# TopLevel.net
KiCad netlist of a schematic drawn in Altium Designer
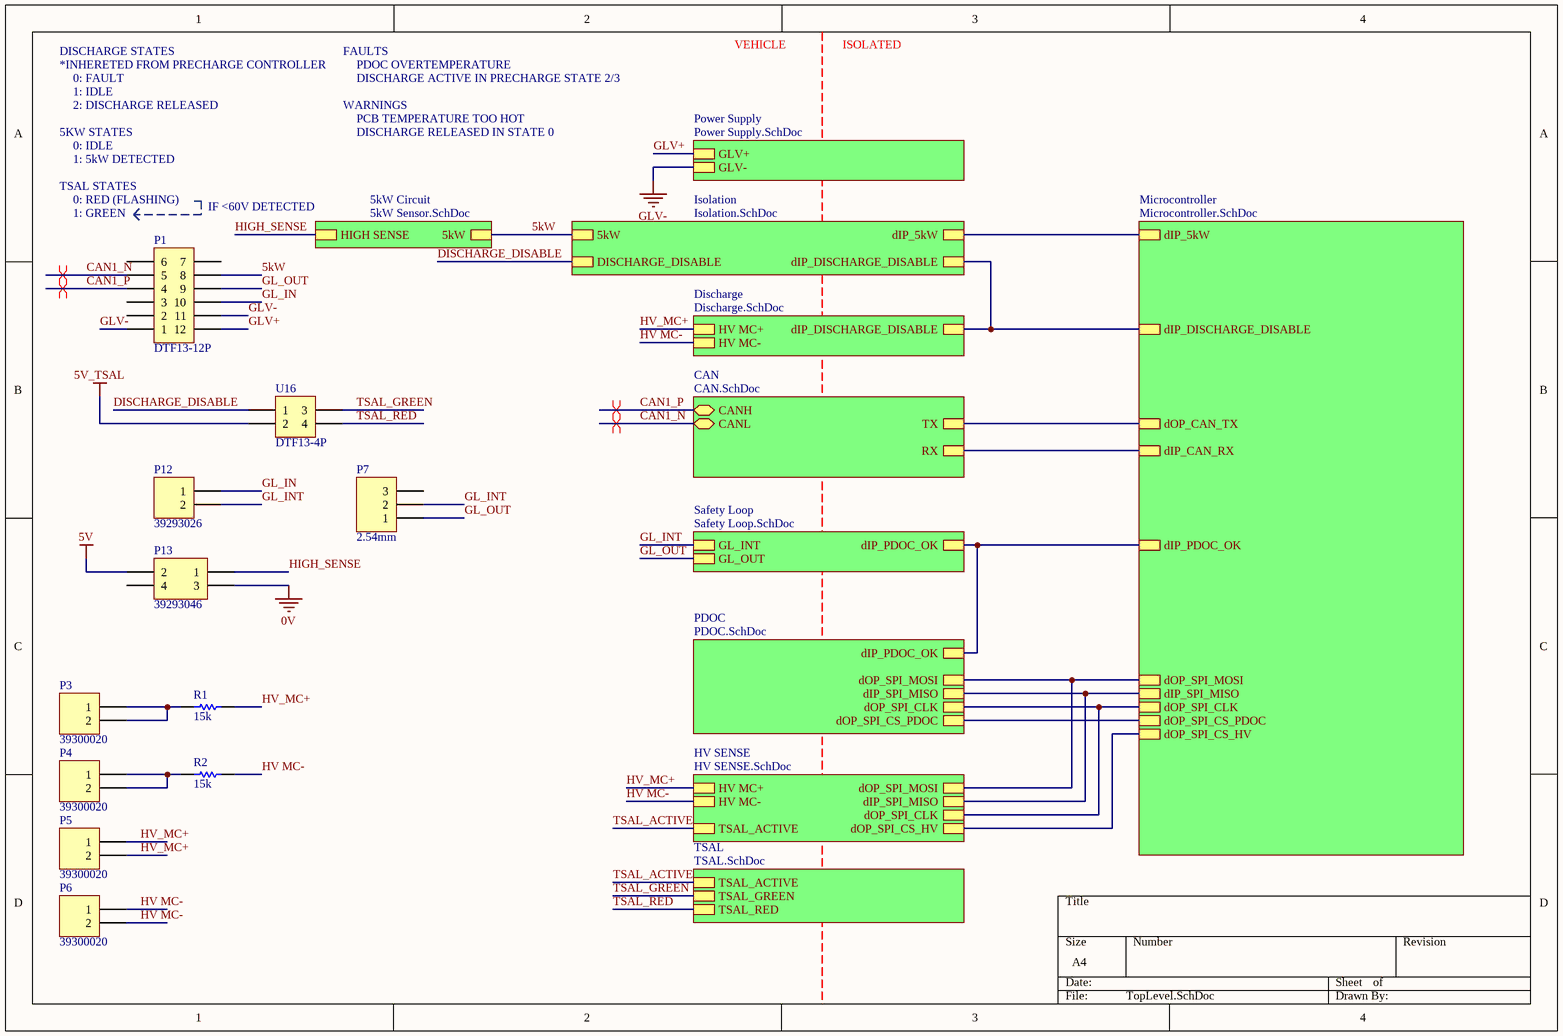
[diagram p0: TopLevel.SchDoc]

(export (version "E")
  (design (tool "Eeschema 10.0.6"))
  (components
    (comp (ref "P1")
      (value "DTF13-12P")
      (footprint "DTF13-12P")
      (fields (field (name "DIGIKEY PART NUMBER") "1734-1861-ND") (field (name "CONTACT") "Copper Alloy"))
      (libsource (lib "ts_standard_connectors") (part "DT13-12P"))
    )
    (comp (ref "P3")
      (value "39300020")
      (footprint "39300020")
      (fields (field (name "DIGIKEY PART NUMBER") "WM21351-ND") (field (name "CONTACT") "Tin"))
      (libsource (lib "ts_standard_connectors") (part "2"))
    )
    (comp (ref "P4")
      (value "39300020")
      (footprint "39300020")
      (fields (field (name "DIGIKEY PART NUMBER") "WM21351-ND") (field (name "CONTACT") "Tin"))
      (libsource (lib "ts_standard_connectors") (part "2"))
    )
    (comp (ref "P5")
      (value "39300020")
      (footprint "39300020")
      (fields (field (name "DIGIKEY PART NUMBER") "WM21351-ND") (field (name "CONTACT") "Tin"))
      (libsource (lib "ts_standard_connectors") (part "2"))
    )
    (comp (ref "P6")
      (value "39300020")
      (footprint "39300020")
      (fields (field (name "DIGIKEY PART NUMBER") "WM21351-ND") (field (name "CONTACT") "Tin"))
      (libsource (lib "ts_standard_connectors") (part "2"))
    )
    (comp (ref "P7")
      (value "2.54mm")
      (footprint "TH 2.54mm Header 1x3")
      (fields (field (name "PART NUMBER") "TH 2.54mm Header 1x3") (field (name "CONTACT") "NA"))
      (libsource (lib "ts_standard_connectors") (part "Header 1x3"))
    )
    (comp (ref "P12")
      (value "39293026")
      (footprint "39293026")
      (fields (field (name "DIGIKEY PART NUMBER") "WM3843-ND") (field (name "CONTACT") "Tin"))
      (libsource (lib "ts_standard_connectors") (part "2"))
    )
    (comp (ref "P13")
      (value "39293046")
      (footprint "39293046")
      (fields (field (name "DIGIKEY PART NUMBER") "WM3844-ND") (field (name "CONTACT") "Tin"))
      (libsource (lib "ts_standard_connectors") (part "4"))
    )
    (comp (ref "R1")
      (value "15k")
      (footprint "TE_SMF7")
      (fields
        (field (name "PART NUMBER") "SMF715KJ")
        (field (name "MANUFACTURER") "TE")
        (field (name "TOLERANCE") "0.05")
      )
      (libsource (lib "ts_standard_library") (part "Resistor"))
    )
    (comp (ref "R2")
      (value "15k")
      (footprint "TE_SMF7")
      (fields
        (field (name "PART NUMBER") "SMF715KJ")
        (field (name "MANUFACTURER") "TE")
        (field (name "TOLERANCE") "0.05")
      )
      (libsource (lib "ts_standard_library") (part "Resistor"))
    )
    (comp (ref "U16")
      (value "DTF13-4P")
      (footprint "DTF13-4P")
      (fields (field (name "DIGIKEY PART NUMBER") "1734-1646-ND") (field (name "CONTACT") "Copper Alloy"))
      (libsource (lib "ts_standard_connectors") (part "DT13-4P"))
    )
  )
  (nets
    (net (code "1") (name "/5kW") (class "Default")
      (node (ref "P1") (pin "8") (pinfunction "8_8") (pintype "passive"))
    )
    (net (code "2") (name "/CAN1_N") (class "Default")
      (node (ref "P1") (pin "5") (pinfunction "5_5") (pintype "power_in"))
    )
    (net (code "3") (name "/CAN1_P") (class "Default")
      (node (ref "P1") (pin "4") (pinfunction "4_4") (pintype "power_in"))
    )
    (net (code "4") (name "/DISCHARGE_DISABLE") (class "Default")
      (node (ref "U16") (pin "1") (pinfunction "1_1") (pintype "power_in"))
    )
    (net (code "5") (name "/GLV+") (class "Default")
      (node (ref "P1") (pin "12") (pinfunction "12_12") (pintype "passive"))
    )
    (net (code "6") (name "/GL_IN") (class "Default")
      (node (ref "P1") (pin "10") (pinfunction "10_10") (pintype "passive"))
      (node (ref "P12") (pin "1") (pinfunction "1_1") (pintype "passive"))
    )
    (net (code "7") (name "/GL_INT") (class "Default")
      (node (ref "P12") (pin "2") (pinfunction "2_2") (pintype "passive"))
      (node (ref "P7") (pin "2") (pinfunction "2_2") (pintype "passive"))
    )
    (net (code "8") (name "/GL_OUT") (class "Default")
      (node (ref "P1") (pin "9") (pinfunction "9_9") (pintype "passive"))
      (node (ref "P7") (pin "1") (pinfunction "1_1") (pintype "passive"))
    )
    (net (code "9") (name "/HIGH_SENSE") (class "Default")
      (node (ref "P13") (pin "1") (pinfunction "1_1") (pintype "passive"))
    )
    (net (code "10") (name "/HV MC-") (class "Default")
      (node (ref "P6") (pin "1") (pinfunction "1_1") (pintype "passive"))
      (node (ref "P6") (pin "2") (pinfunction "2_2") (pintype "passive"))
      (node (ref "R2") (pin "2") (pinfunction "2_2") (pintype "passive"))
    )
    (net (code "11") (name "/HV_MC+") (class "Default")
      (node (ref "P5") (pin "1") (pinfunction "1_1") (pintype "passive"))
      (node (ref "P5") (pin "2") (pinfunction "2_2") (pintype "passive"))
      (node (ref "R1") (pin "2") (pinfunction "2_2") (pintype "passive"))
    )
    (net (code "14") (name "/TSAL_GREEN") (class "Default")
      (node (ref "U16") (pin "3") (pinfunction "3_3") (pintype "passive"))
    )
    (net (code "15") (name "/TSAL_RED") (class "Default")
      (node (ref "U16") (pin "4") (pinfunction "4_4") (pintype "passive"))
    )
    (net (code "25") (name "0V") (class "Default")
      (node (ref "P13") (pin "3") (pinfunction "3_3") (pintype "passive"))
    )
    (net (code "26") (name "5V") (class "Default")
      (node (ref "P13") (pin "2") (pinfunction "2_2") (pintype "passive"))
    )
    (net (code "27") (name "5V_TSAL") (class "Default")
      (node (ref "U16") (pin "2") (pinfunction "2_2") (pintype "power_in"))
    )
    (net (code "28") (name "GLV-") (class "Default")
      (node (ref "P1") (pin "1") (pinfunction "1_1") (pintype "power_in"))
      (node (ref "P1") (pin "11") (pinfunction "11_11") (pintype "passive"))
    )
    (net (code "29") (name "Net-(P3-Pad1)") (class "Default")
      (node (ref "P3") (pin "1") (pinfunction "1_1") (pintype "passive"))
      (node (ref "P3") (pin "2") (pinfunction "2_2") (pintype "passive"))
      (node (ref "R1") (pin "1") (pinfunction "1_1") (pintype "passive"))
    )
    (net (code "30") (name "Net-(P4-Pad1)") (class "Default")
      (node (ref "P4") (pin "1") (pinfunction "1_1") (pintype "passive"))
      (node (ref "P4") (pin "2") (pinfunction "2_2") (pintype "passive"))
      (node (ref "R2") (pin "1") (pinfunction "1_1") (pintype "passive"))
    )
    (net (code "31") (name "unconnected-(P1-Pad2)") (class "Default")
      (node (ref "P1") (pin "2") (pinfunction "2_2") (pintype "power_in"))
    )
    (net (code "32") (name "unconnected-(P1-Pad3)") (class "Default")
      (node (ref "P1") (pin "3") (pinfunction "3_3") (pintype "power_in"))
    )
    (net (code "33") (name "unconnected-(P1-Pad6)") (class "Default")
      (node (ref "P1") (pin "6") (pinfunction "6_6") (pintype "power_in"))
    )
    (net (code "34") (name "unconnected-(P1-Pad7)") (class "Default")
      (node (ref "P1") (pin "7") (pinfunction "7_7") (pintype "passive"))
    )
    (net (code "35") (name "unconnected-(P7-Pad3)") (class "Default")
      (node (ref "P7") (pin "3") (pinfunction "3_3") (pintype "passive"))
    )
    (net (code "36") (name "unconnected-(P13-Pad4)") (class "Default")
      (node (ref "P13") (pin "4") (pinfunction "4_4") (pintype "passive"))
    )
  )
)
